# MotorController.net
KiCad netlist of a schematic drawn in EAGLE
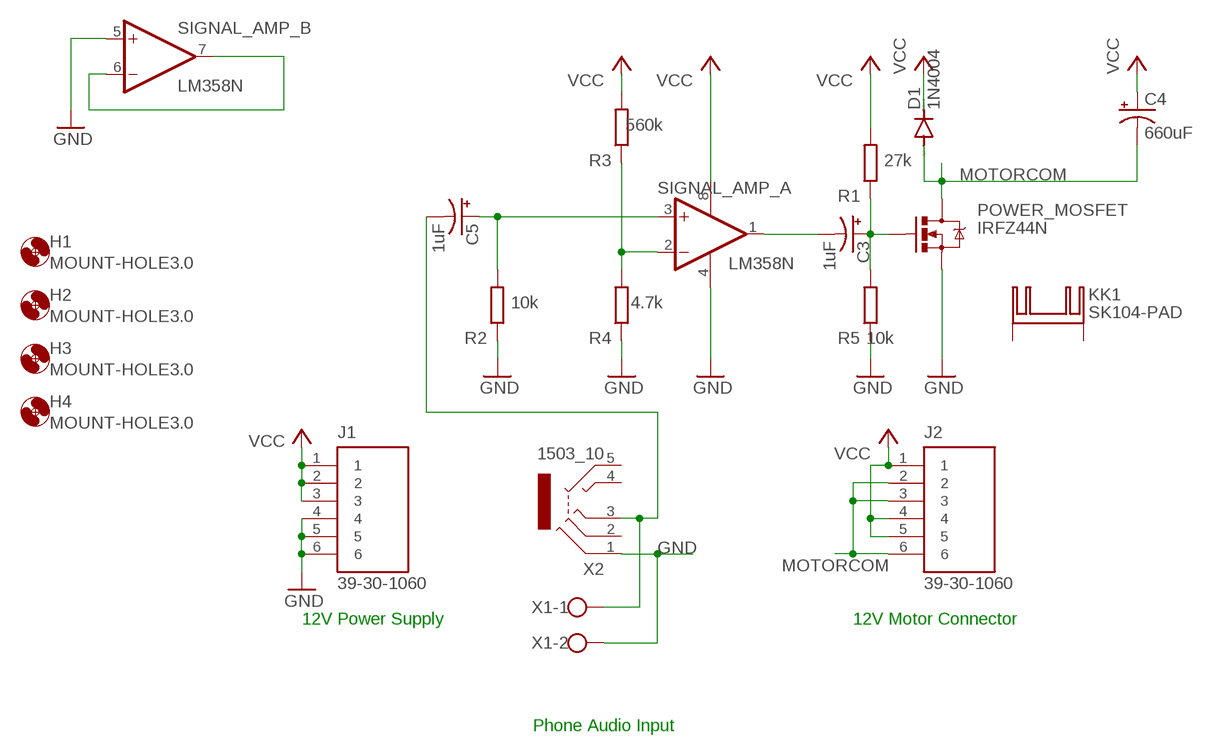
[diagram p0: schematic, sheet 1]

(export (version "E")
  (design (tool "Eeschema 10.0.6"))
  (components
    (comp (ref "C3")
      (value "1uF")
      (footprint "eagle-import:E2,5-7")
      (libsource (lib "eagle-import") (part "CPOL-USE2.5-7"))
    )
    (comp (ref "C4")
      (value "660uF")
      (footprint "eagle-import:E5-10,5")
      (libsource (lib "eagle-import") (part "CPOL-USE5-10.5"))
    )
    (comp (ref "C5")
      (value "1uF")
      (footprint "eagle-import:E2,5-7")
      (libsource (lib "eagle-import") (part "CPOL-USE2.5-7"))
    )
    (comp (ref "D1")
      (value "1N4004")
      (footprint "eagle-import:DO41-10")
      (libsource (lib "eagle-import") (part "1N4004"))
    )
    (comp (ref "H1")
      (value "MOUNT-HOLE3.0")
      (footprint "eagle-import:3,0")
      (libsource (lib "eagle-import") (part "MOUNT-HOLE3.0"))
    )
    (comp (ref "H2")
      (value "MOUNT-HOLE3.0")
      (footprint "eagle-import:3,0")
      (libsource (lib "eagle-import") (part "MOUNT-HOLE3.0"))
    )
    (comp (ref "H3")
      (value "MOUNT-HOLE3.0")
      (footprint "eagle-import:3,0")
      (libsource (lib "eagle-import") (part "MOUNT-HOLE3.0"))
    )
    (comp (ref "H4")
      (value "MOUNT-HOLE3.0")
      (footprint "eagle-import:3,0")
      (libsource (lib "eagle-import") (part "MOUNT-HOLE3.0"))
    )
    (comp (ref "J1")
      (value "39-30-1060")
      (footprint "eagle-import:MOLEX_39-30-1060")
      (fields (field (name "MF") "Molex"))
      (libsource (lib "eagle-import") (part "39-30-1060"))
    )
    (comp (ref "J2")
      (value "39-30-1060")
      (footprint "eagle-import:MOLEX_39-30-1060")
      (fields (field (name "MF") "Molex"))
      (libsource (lib "eagle-import") (part "39-30-1060"))
    )
    (comp (ref "KK1")
      (value "SK104-PAD")
      (footprint "eagle-import:SK104-PAD")
      (libsource (lib "eagle-import") (part "SK104-PAD"))
    )
    (comp (ref "POWER_MOSFET")
      (value "IRFZ44N")
      (footprint "eagle-import:TO-220")
      (fields (field (name "MF") "Infineon Technologies"))
      (libsource (lib "eagle-import") (part "IRFZ44N"))
    )
    (comp (ref "R1")
      (value "27k")
      (footprint "eagle-import:0204_7")
      (libsource (lib "eagle-import") (part "R-EU_0204/7"))
    )
    (comp (ref "R2")
      (value "10k")
      (footprint "eagle-import:0204_7")
      (libsource (lib "eagle-import") (part "R-EU_0204/7"))
    )
    (comp (ref "R3")
      (value "560k")
      (footprint "eagle-import:0204_7")
      (libsource (lib "eagle-import") (part "R-EU_0204/7"))
    )
    (comp (ref "R4")
      (value "4.7k")
      (footprint "eagle-import:0204_7")
      (libsource (lib "eagle-import") (part "R-EU_0204/7"))
    )
    (comp (ref "R5")
      (value "10k")
      (footprint "eagle-import:0204_7")
      (libsource (lib "eagle-import") (part "R-EU_0204/7"))
    )
    (comp (ref "SIGNAL_AMP_")
      (value "LM358N")
      (footprint "eagle-import:DIL08")
      (libsource (lib "eagle-import") (part "LM358N"))
    )
    (comp (ref "X1")
      (value "W237-102")
      (footprint "eagle-import:W237-102")
      (fields (field (name "MPN") "237-102"))
      (libsource (lib "eagle-import") (part "W237-102"))
    )
    (comp (ref "X2")
      (value "1503_10")
      (footprint "eagle-import:1503_10")
      (libsource (lib "eagle-import") (part "1503_10"))
    )
  )
  (nets
    (net (code "1") (name "/MOTORCOM") (class "Default")
      (node (ref "C4") (pin "-") (pinfunction "-_-") (pintype "passive"))
      (node (ref "D1") (pin "A") (pinfunction "A_A") (pintype "passive"))
      (node (ref "J2") (pin "2") (pinfunction "2_2") (pintype "passive"))
      (node (ref "J2") (pin "3") (pinfunction "3_3") (pintype "passive"))
      (node (ref "J2") (pin "6") (pinfunction "6_6") (pintype "passive"))
      (node (ref "POWER_MOSFET") (pin "2") (pinfunction "D_2") (pintype "passive"))
    )
    (net (code "2") (name "GND") (class "Default")
      (node (ref "J1") (pin "4") (pinfunction "4_4") (pintype "passive"))
      (node (ref "J1") (pin "5") (pinfunction "5_5") (pintype "passive"))
      (node (ref "J1") (pin "6") (pinfunction "6_6") (pintype "passive"))
      (node (ref "POWER_MOSFET") (pin "3") (pinfunction "S_3") (pintype "passive"))
      (node (ref "R2") (pin "1") (pinfunction "1_1") (pintype "passive"))
      (node (ref "R4") (pin "1") (pinfunction "1_1") (pintype "passive"))
      (node (ref "R5") (pin "1") (pinfunction "1_1") (pintype "passive"))
      (node (ref "SIGNAL_AMP_") (pin "4") (pinfunction "V-_4") (pintype "power_in"))
      (node (ref "SIGNAL_AMP_") (pin "5") (pinfunction "+IN_5") (pintype "input"))
      (node (ref "X1") (pin "2") (pinfunction "KL_2") (pintype "passive"))
      (node (ref "X2") (pin "1") (pinfunction "1_1") (pintype "passive"))
    )
    (net (code "3") (name "Net-(POWER_MOSFET-G)") (class "Default")
      (node (ref "C3") (pin "+") (pinfunction "+_+") (pintype "passive"))
      (node (ref "POWER_MOSFET") (pin "1") (pinfunction "G_1") (pintype "passive"))
      (node (ref "R1") (pin "1") (pinfunction "1_1") (pintype "passive"))
      (node (ref "R5") (pin "2") (pinfunction "2_2") (pintype "passive"))
    )
    (net (code "4") (name "Net-(SIGNAL_AMP_A-+IN)") (class "Default")
      (node (ref "C5") (pin "+") (pinfunction "+_+") (pintype "passive"))
      (node (ref "R2") (pin "2") (pinfunction "2_2") (pintype "passive"))
      (node (ref "SIGNAL_AMP_") (pin "3") (pinfunction "+IN_3") (pintype "input"))
    )
    (net (code "5") (name "Net-(SIGNAL_AMP_A--IN)") (class "Default")
      (node (ref "R3") (pin "1") (pinfunction "1_1") (pintype "passive"))
      (node (ref "R4") (pin "2") (pinfunction "2_2") (pintype "passive"))
      (node (ref "SIGNAL_AMP_") (pin "2") (pinfunction "-IN_2") (pintype "input"))
    )
    (net (code "6") (name "Net-(SIGNAL_AMP_A-OUT)") (class "Default")
      (node (ref "C3") (pin "-") (pinfunction "-_-") (pintype "passive"))
      (node (ref "SIGNAL_AMP_") (pin "1") (pinfunction "OUT_1") (pintype "output"))
    )
    (net (code "7") (name "Net-(SIGNAL_AMP_B--IN)") (class "Default")
      (node (ref "SIGNAL_AMP_") (pin "6") (pinfunction "-IN_6") (pintype "input"))
      (node (ref "SIGNAL_AMP_") (pin "7") (pinfunction "OUT_7") (pintype "output"))
    )
    (net (code "8") (name "Net-(X1A-KL)") (class "Default")
      (node (ref "C5") (pin "-") (pinfunction "-_-") (pintype "passive"))
      (node (ref "X1") (pin "1") (pinfunction "KL_1") (pintype "passive"))
      (node (ref "X2") (pin "3") (pinfunction "3_3") (pintype "passive"))
    )
    (net (code "9") (name "VCC") (class "Default")
      (node (ref "C4") (pin "+") (pinfunction "+_+") (pintype "passive"))
      (node (ref "D1") (pin "C") (pinfunction "C_C") (pintype "passive"))
      (node (ref "J1") (pin "1") (pinfunction "1_1") (pintype "passive"))
      (node (ref "J1") (pin "2") (pinfunction "2_2") (pintype "passive"))
      (node (ref "J1") (pin "3") (pinfunction "3_3") (pintype "passive"))
      (node (ref "J2") (pin "1") (pinfunction "1_1") (pintype "passive"))
      (node (ref "J2") (pin "4") (pinfunction "4_4") (pintype "passive"))
      (node (ref "J2") (pin "5") (pinfunction "5_5") (pintype "passive"))
      (node (ref "R1") (pin "2") (pinfunction "2_2") (pintype "passive"))
      (node (ref "R3") (pin "2") (pinfunction "2_2") (pintype "passive"))
      (node (ref "SIGNAL_AMP_") (pin "8") (pinfunction "V+_8") (pintype "power_in"))
    )
    (net (code "10") (name "unconnected-(KK1-K-PadK1)") (class "Default")
      (node (ref "KK1") (pin "K1") (pinfunction "K_K1") (pintype "passive"))
    )
    (net (code "11") (name "unconnected-(KK1-K-PadK2)") (class "Default")
      (node (ref "KK1") (pin "K2") (pinfunction "K_K2") (pintype "passive"))
    )
    (net (code "12") (name "unconnected-(X2-Pad2)") (class "Default")
      (node (ref "X2") (pin "2") (pinfunction "2_2") (pintype "passive"))
    )
    (net (code "13") (name "unconnected-(X2-Pad4)") (class "Default")
      (node (ref "X2") (pin "4") (pinfunction "4_4") (pintype "passive"))
    )
    (net (code "14") (name "unconnected-(X2-Pad5)") (class "Default")
      (node (ref "X2") (pin "5") (pinfunction "5_5") (pintype "passive"))
    )
  )
)
